# encantado.net
KiCad netlist of a schematic drawn in EAGLE
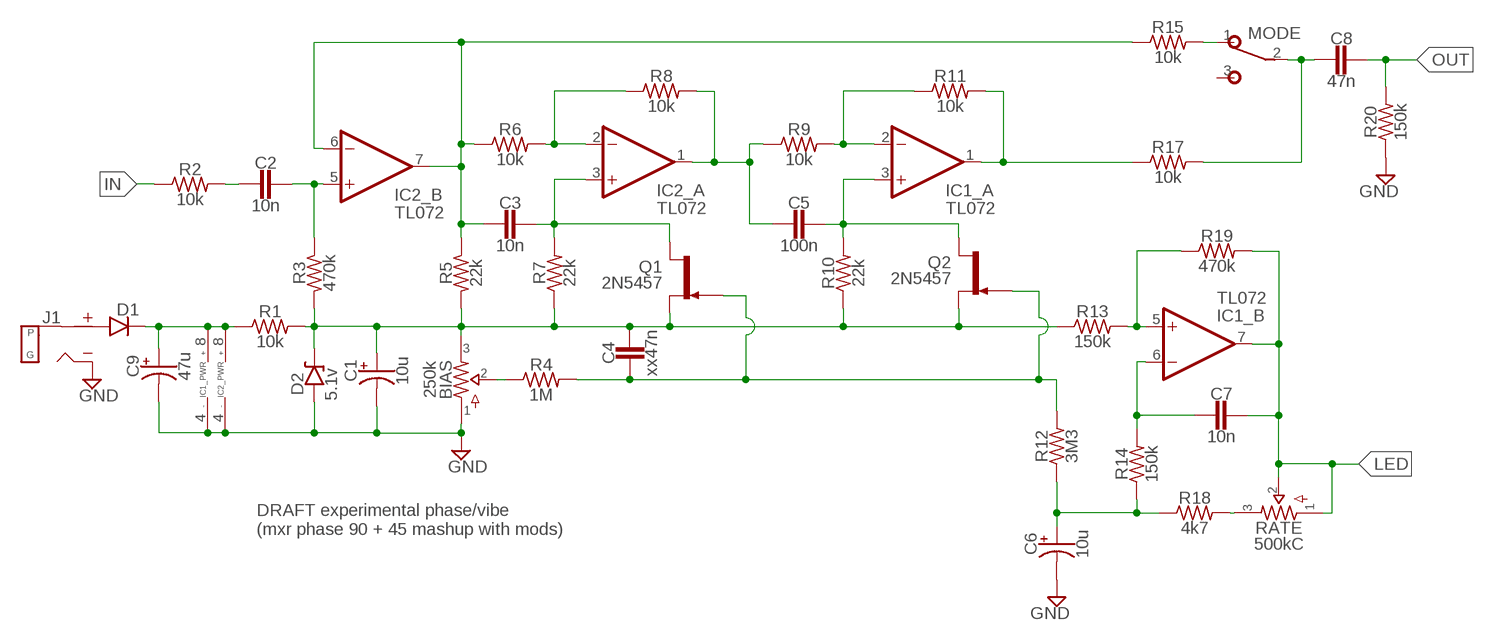
[diagram p0: schematic, sheet 1]

(export (version "E")
  (design (tool "Eeschema 10.0.6"))
  (components
    (comp (ref "BIAS")
      (value "250k")
      (footprint "eagle-import:2262_TRIM")
      (libsource (lib "eagle-import") (part "POTSTRIM"))
    )
    (comp (ref "C1")
      (value "10u")
      (footprint "eagle-import:050_020_1B")
      (libsource (lib "eagle-import") (part "0501B"))
    )
    (comp (ref "C2")
      (value "10n")
      (footprint "eagle-import:050X030_025_2")
      (libsource (lib "eagle-import") (part "CER/FILM2"))
    )
    (comp (ref "C3")
      (value "10n")
      (footprint "eagle-import:050X030_025_2")
      (libsource (lib "eagle-import") (part "CER/FILM2"))
    )
    (comp (ref "C4")
      (value "xx47n")
      (footprint "eagle-import:050X030_025_2")
      (libsource (lib "eagle-import") (part "CER/FILM2"))
    )
    (comp (ref "C5")
      (value "100n")
      (footprint "eagle-import:050X030_025_2")
      (libsource (lib "eagle-import") (part "CER/FILM2"))
    )
    (comp (ref "C6")
      (value "10u")
      (footprint "eagle-import:050_020_1B")
      (libsource (lib "eagle-import") (part "0501B"))
    )
    (comp (ref "C7")
      (value "10n")
      (footprint "eagle-import:050X030_025_2")
      (libsource (lib "eagle-import") (part "CER/FILM2"))
    )
    (comp (ref "C8")
      (value "47n")
      (footprint "eagle-import:050X030_025_2")
      (libsource (lib "eagle-import") (part "CER/FILM2"))
    )
    (comp (ref "C9")
      (value "47u")
      (footprint "eagle-import:050_020_1B")
      (libsource (lib "eagle-import") (part "0501B"))
    )
    (comp (ref "D1")
      (value "DO35.3")
      (footprint "eagle-import:DO35-3")
      (libsource (lib "eagle-import") (part "DO35.3"))
    )
    (comp (ref "D2")
      (value "5.1v")
      (footprint "eagle-import:DO41-3")
      (libsource (lib "eagle-import") (part "ZENER.3"))
    )
    (comp (ref "IC1")
      (value "TL072")
      (footprint "eagle-import:DIL08")
      (libsource (lib "eagle-import") (part "DUALTH"))
    )
    (comp (ref "IC2")
      (value "TL072")
      (footprint "eagle-import:DIL08")
      (libsource (lib "eagle-import") (part "DUALTH"))
    )
    (comp (ref "J1")
      (value "DC_MONO")
      (footprint "eagle-import:DC")
      (libsource (lib "eagle-import") (part "DC_MONO"))
    )
    (comp (ref "MODE")
      (value "SPDTPADS")
      (footprint "eagle-import:SPDT")
      (libsource (lib "eagle-import") (part "SPDTPADS"))
    )
    (comp (ref "Q1")
      (value "2N5457")
      (footprint "eagle-import:TO92-")
      (libsource (lib "eagle-import") (part "2N5457"))
    )
    (comp (ref "Q2")
      (value "2N5457")
      (footprint "eagle-import:TO92-")
      (libsource (lib "eagle-import") (part "2N5457"))
    )
    (comp (ref "R1")
      (value "10k")
      (footprint "eagle-import:R0207_2V")
      (libsource (lib "eagle-import") (part "R_.2"))
    )
    (comp (ref "R2")
      (value "10k")
      (footprint "eagle-import:R0207_2V")
      (libsource (lib "eagle-import") (part "R_.2"))
    )
    (comp (ref "R3")
      (value "470k")
      (footprint "eagle-import:R0207_2V")
      (libsource (lib "eagle-import") (part "R_.2"))
    )
    (comp (ref "R4")
      (value "1M")
      (footprint "eagle-import:R0207_2V")
      (libsource (lib "eagle-import") (part "R_.2"))
    )
    (comp (ref "R5")
      (value "22k")
      (footprint "eagle-import:R0207_2V")
      (libsource (lib "eagle-import") (part "R_.2"))
    )
    (comp (ref "R6")
      (value "10k")
      (footprint "eagle-import:R0207_2V")
      (libsource (lib "eagle-import") (part "R_.2"))
    )
    (comp (ref "R7")
      (value "22k")
      (footprint "eagle-import:R0207_2V")
      (libsource (lib "eagle-import") (part "R_.2"))
    )
    (comp (ref "R8")
      (value "10k")
      (footprint "eagle-import:R0207_2V")
      (libsource (lib "eagle-import") (part "R_.2"))
    )
    (comp (ref "R9")
      (value "10k")
      (footprint "eagle-import:R0207_2V")
      (libsource (lib "eagle-import") (part "R_.2"))
    )
    (comp (ref "R10")
      (value "22k")
      (footprint "eagle-import:R0207_2V")
      (libsource (lib "eagle-import") (part "R_.2"))
    )
    (comp (ref "R11")
      (value "10k")
      (footprint "eagle-import:R0207_2V")
      (libsource (lib "eagle-import") (part "R_.2"))
    )
    (comp (ref "R12")
      (value "3M3")
      (footprint "eagle-import:R0207_2V")
      (libsource (lib "eagle-import") (part "R_.2"))
    )
    (comp (ref "R13")
      (value "150k")
      (footprint "eagle-import:R0207_2V")
      (libsource (lib "eagle-import") (part "R_.2"))
    )
    (comp (ref "R14")
      (value "150k")
      (footprint "eagle-import:R0207_2V")
      (libsource (lib "eagle-import") (part "R_.2"))
    )
    (comp (ref "R15")
      (value "10k")
      (footprint "eagle-import:R0207_2V")
      (libsource (lib "eagle-import") (part "R_.2"))
    )
    (comp (ref "R17")
      (value "10k")
      (footprint "eagle-import:R0207_2V")
      (libsource (lib "eagle-import") (part "R_.2"))
    )
    (comp (ref "R18")
      (value "4k7")
      (footprint "eagle-import:R0207_2V")
      (libsource (lib "eagle-import") (part "R_.2"))
    )
    (comp (ref "R19")
      (value "470k")
      (footprint "eagle-import:R0207_2V")
      (libsource (lib "eagle-import") (part "R_.2"))
    )
    (comp (ref "R20")
      (value "150k")
      (footprint "eagle-import:R0207_2V")
      (libsource (lib "eagle-import") (part "R_.2"))
    )
    (comp (ref "RATE")
      (value "500kC")
      (footprint "eagle-import:2262_TRIM")
      (libsource (lib "eagle-import") (part "POTSTRIM"))
    )
  )
  (nets
    (net (code "1") (name "/S_OUT") (class "Default")
      (node (ref "C5") (pin "1") (pinfunction "1_1") (pintype "passive"))
      (node (ref "IC1") (pin "1") (pinfunction "OUT_1") (pintype "output"))
      (node (ref "IC2") (pin "1") (pinfunction "OUT_1") (pintype "output"))
      (node (ref "R11") (pin "2") (pinfunction "2_2") (pintype "passive"))
      (node (ref "R17") (pin "1") (pinfunction "1_1") (pintype "passive"))
      (node (ref "R8") (pin "2") (pinfunction "2_2") (pintype "passive"))
      (node (ref "R9") (pin "1") (pinfunction "1_1") (pintype "passive"))
    )
    (net (code "2") (name "GND") (class "Default")
      (node (ref "BIAS") (pin "1") (pinfunction "1_1") (pintype "passive"))
      (node (ref "C1") (pin "-") (pinfunction "-_-") (pintype "passive"))
      (node (ref "C6") (pin "-") (pinfunction "-_-") (pintype "passive"))
      (node (ref "C9") (pin "-") (pinfunction "-_-") (pintype "passive"))
      (node (ref "D2") (pin "A") (pinfunction "A_A") (pintype "passive"))
      (node (ref "IC1") (pin "4") (pinfunction "V-_4") (pintype "power_in"))
      (node (ref "IC2") (pin "4") (pinfunction "V-_4") (pintype "power_in"))
      (node (ref "J1") (pin "S") (pinfunction "SLEEVE_S") (pintype "passive"))
      (node (ref "R20") (pin "1") (pinfunction "1_1") (pintype "passive"))
    )
    (net (code "3") (name "IN") (class "Default")
      (node (ref "R2") (pin "1") (pinfunction "1_1") (pintype "passive"))
    )
    (net (code "4") (name "LED") (class "Default")
      (node (ref "C7") (pin "2") (pinfunction "2_2") (pintype "passive"))
      (node (ref "IC1") (pin "7") (pinfunction "OUT_7") (pintype "output"))
      (node (ref "R19") (pin "2") (pinfunction "2_2") (pintype "passive"))
      (node (ref "RATE") (pin "1") (pinfunction "1_1") (pintype "passive"))
      (node (ref "RATE") (pin "2") (pinfunction "2_2") (pintype "passive"))
    )
    (net (code "5") (name "Net-(BIAS-Pad2)") (class "Default")
      (node (ref "BIAS") (pin "2") (pinfunction "2_2") (pintype "passive"))
      (node (ref "R4") (pin "1") (pinfunction "1_1") (pintype "passive"))
    )
    (net (code "6") (name "Net-(C2-Pad1)") (class "Default")
      (node (ref "C2") (pin "1") (pinfunction "1_1") (pintype "passive"))
      (node (ref "R2") (pin "2") (pinfunction "2_2") (pintype "passive"))
    )
    (net (code "7") (name "Net-(C6-Pad+)") (class "Default")
      (node (ref "C6") (pin "+") (pinfunction "+_+") (pintype "passive"))
      (node (ref "R12") (pin "1") (pinfunction "1_1") (pintype "passive"))
      (node (ref "R14") (pin "1") (pinfunction "1_1") (pintype "passive"))
      (node (ref "R18") (pin "1") (pinfunction "1_1") (pintype "passive"))
    )
    (net (code "8") (name "Net-(IC1A-+IN)") (class "Default")
      (node (ref "C5") (pin "2") (pinfunction "2_2") (pintype "passive"))
      (node (ref "IC1") (pin "3") (pinfunction "+IN_3") (pintype "input"))
      (node (ref "Q2") (pin "3") (pinfunction "D_3") (pintype "passive"))
      (node (ref "R10") (pin "2") (pinfunction "2_2") (pintype "passive"))
    )
    (net (code "9") (name "Net-(IC1A--IN)") (class "Default")
      (node (ref "IC1") (pin "2") (pinfunction "-IN_2") (pintype "input"))
      (node (ref "R11") (pin "1") (pinfunction "1_1") (pintype "passive"))
      (node (ref "R9") (pin "2") (pinfunction "2_2") (pintype "passive"))
    )
    (net (code "10") (name "Net-(IC1B-+IN)") (class "Default")
      (node (ref "IC1") (pin "5") (pinfunction "+IN_5") (pintype "input"))
      (node (ref "R13") (pin "2") (pinfunction "2_2") (pintype "passive"))
      (node (ref "R19") (pin "1") (pinfunction "1_1") (pintype "passive"))
    )
    (net (code "11") (name "Net-(IC1B--IN)") (class "Default")
      (node (ref "C7") (pin "1") (pinfunction "1_1") (pintype "passive"))
      (node (ref "IC1") (pin "6") (pinfunction "-IN_6") (pintype "input"))
      (node (ref "R14") (pin "2") (pinfunction "2_2") (pintype "passive"))
    )
    (net (code "12") (name "Net-(IC1C-V+)") (class "Default")
      (node (ref "C9") (pin "+") (pinfunction "+_+") (pintype "passive"))
      (node (ref "D1") (pin "C") (pinfunction "C_C") (pintype "passive"))
      (node (ref "IC1") (pin "8") (pinfunction "V+_8") (pintype "power_in"))
      (node (ref "IC2") (pin "8") (pinfunction "V+_8") (pintype "power_in"))
      (node (ref "R1") (pin "1") (pinfunction "1_1") (pintype "passive"))
    )
    (net (code "13") (name "Net-(IC2A-+IN)") (class "Default")
      (node (ref "C3") (pin "2") (pinfunction "2_2") (pintype "passive"))
      (node (ref "IC2") (pin "3") (pinfunction "+IN_3") (pintype "input"))
      (node (ref "Q1") (pin "3") (pinfunction "D_3") (pintype "passive"))
      (node (ref "R7") (pin "2") (pinfunction "2_2") (pintype "passive"))
    )
    (net (code "14") (name "Net-(IC2A--IN)") (class "Default")
      (node (ref "IC2") (pin "2") (pinfunction "-IN_2") (pintype "input"))
      (node (ref "R6") (pin "2") (pinfunction "2_2") (pintype "passive"))
      (node (ref "R8") (pin "1") (pinfunction "1_1") (pintype "passive"))
    )
    (net (code "15") (name "Net-(IC2B-+IN)") (class "Default")
      (node (ref "C2") (pin "2") (pinfunction "2_2") (pintype "passive"))
      (node (ref "IC2") (pin "5") (pinfunction "+IN_5") (pintype "input"))
      (node (ref "R3") (pin "1") (pinfunction "1_1") (pintype "passive"))
    )
    (net (code "16") (name "Net-(IC2B--IN)") (class "Default")
      (node (ref "C3") (pin "1") (pinfunction "1_1") (pintype "passive"))
      (node (ref "IC2") (pin "6") (pinfunction "-IN_6") (pintype "input"))
      (node (ref "IC2") (pin "7") (pinfunction "OUT_7") (pintype "output"))
      (node (ref "R15") (pin "1") (pinfunction "1_1") (pintype "passive"))
      (node (ref "R5") (pin "1") (pinfunction "1_1") (pintype "passive"))
      (node (ref "R6") (pin "1") (pinfunction "1_1") (pintype "passive"))
    )
    (net (code "17") (name "Net-(J1-TIP)") (class "Default")
      (node (ref "D1") (pin "A") (pinfunction "A_A") (pintype "passive"))
      (node (ref "J1") (pin "T") (pinfunction "TIP_T") (pintype "passive"))
    )
    (net (code "18") (name "Net-(MODE-O)") (class "Default")
      (node (ref "MODE") (pin "1") (pinfunction "O_1") (pintype "passive"))
      (node (ref "R15") (pin "2") (pinfunction "2_2") (pintype "passive"))
    )
    (net (code "19") (name "Net-(MODE-P)") (class "Default")
      (node (ref "C8") (pin "1") (pinfunction "1_1") (pintype "passive"))
      (node (ref "MODE") (pin "2") (pinfunction "P_2") (pintype "passive"))
      (node (ref "R17") (pin "2") (pinfunction "2_2") (pintype "passive"))
    )
    (net (code "20") (name "Net-(Q1-G)") (class "Default")
      (node (ref "C4") (pin "1") (pinfunction "1_1") (pintype "passive"))
      (node (ref "Q1") (pin "1") (pinfunction "G_1") (pintype "passive"))
      (node (ref "Q2") (pin "1") (pinfunction "G_1") (pintype "passive"))
      (node (ref "R12") (pin "2") (pinfunction "2_2") (pintype "passive"))
      (node (ref "R4") (pin "2") (pinfunction "2_2") (pintype "passive"))
    )
    (net (code "21") (name "Net-(Q1-S)") (class "Default")
      (node (ref "BIAS") (pin "3") (pinfunction "3_3") (pintype "passive"))
      (node (ref "C1") (pin "+") (pinfunction "+_+") (pintype "passive"))
      (node (ref "C4") (pin "2") (pinfunction "2_2") (pintype "passive"))
      (node (ref "D2") (pin "C") (pinfunction "C_C") (pintype "passive"))
      (node (ref "Q1") (pin "2") (pinfunction "S_2") (pintype "passive"))
      (node (ref "Q2") (pin "2") (pinfunction "S_2") (pintype "passive"))
      (node (ref "R1") (pin "2") (pinfunction "2_2") (pintype "passive"))
      (node (ref "R10") (pin "1") (pinfunction "1_1") (pintype "passive"))
      (node (ref "R13") (pin "1") (pinfunction "1_1") (pintype "passive"))
      (node (ref "R3") (pin "2") (pinfunction "2_2") (pintype "passive"))
      (node (ref "R5") (pin "2") (pinfunction "2_2") (pintype "passive"))
      (node (ref "R7") (pin "1") (pinfunction "1_1") (pintype "passive"))
    )
    (net (code "22") (name "Net-(R18-Pad2)") (class "Default")
      (node (ref "R18") (pin "2") (pinfunction "2_2") (pintype "passive"))
      (node (ref "RATE") (pin "3") (pinfunction "3_3") (pintype "passive"))
    )
    (net (code "23") (name "OUT") (class "Default")
      (node (ref "C8") (pin "2") (pinfunction "2_2") (pintype "passive"))
      (node (ref "R20") (pin "2") (pinfunction "2_2") (pintype "passive"))
    )
    (net (code "24") (name "unconnected-(MODE-S-Pad3)") (class "Default")
      (node (ref "MODE") (pin "3") (pinfunction "S_3") (pintype "passive"))
    )
  )
)
